# Thermistors.net
KiCad netlist of a schematic drawn in Altium Designer
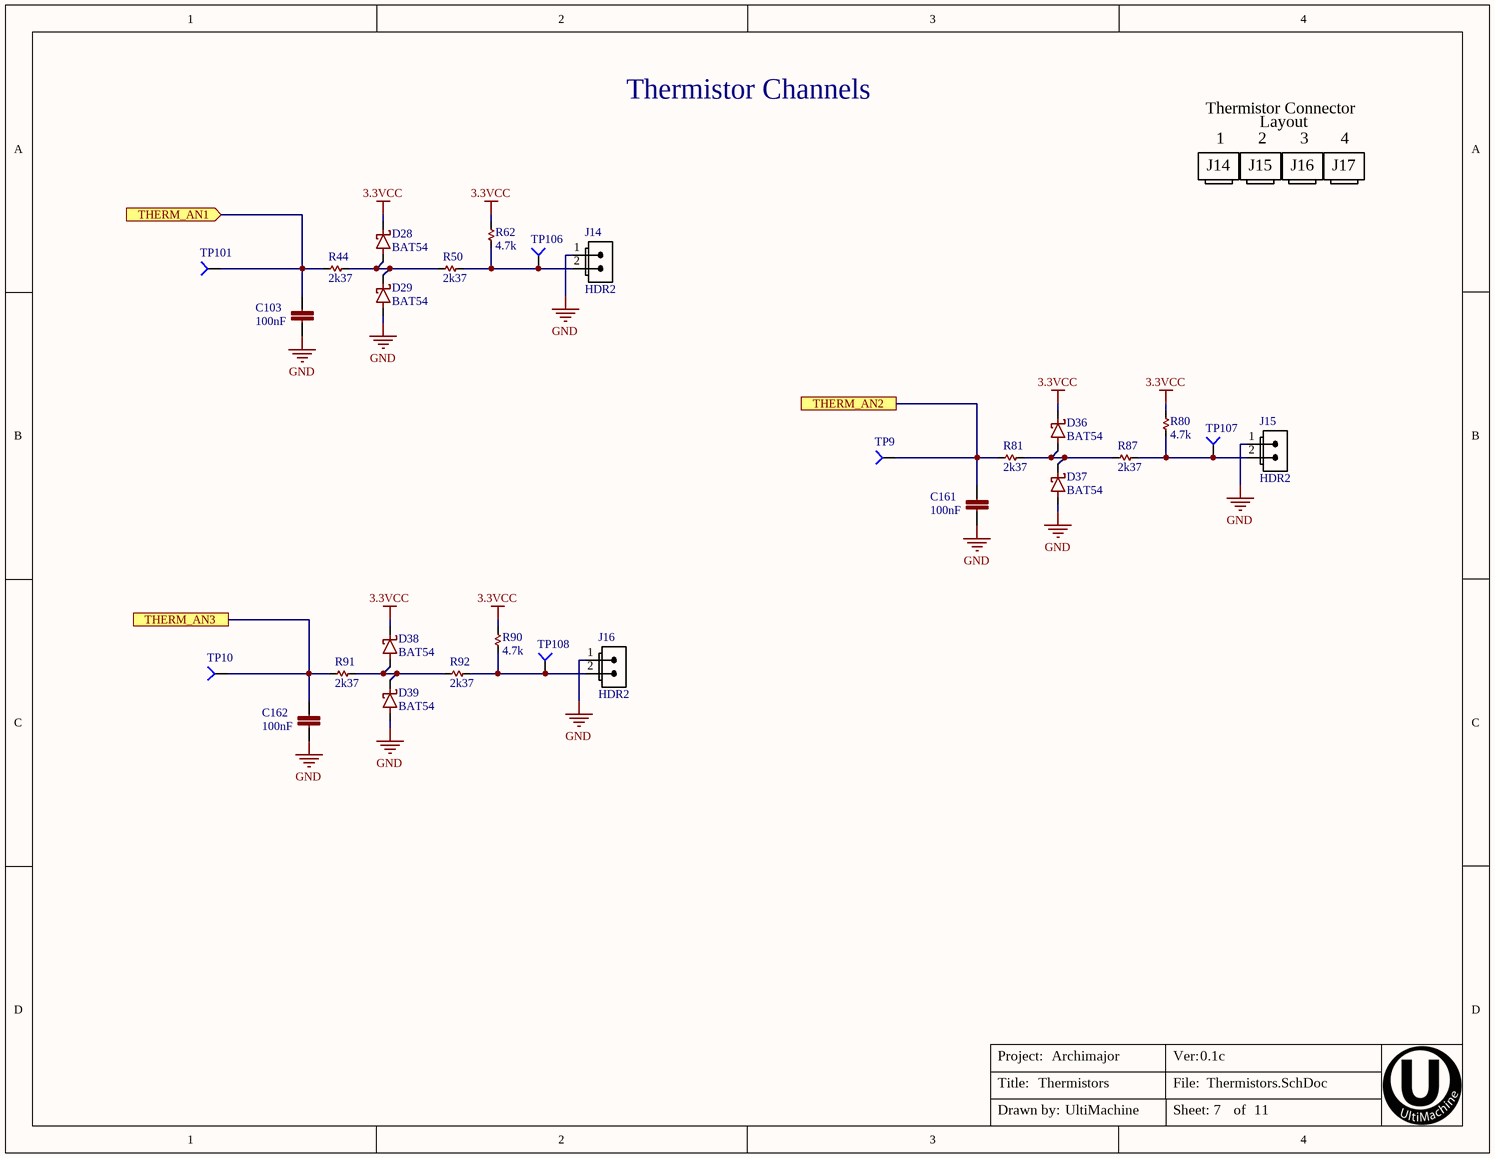
[diagram p0: Thermistors.SchDoc]

(export (version "E")
  (design (tool "Eeschema 10.0.6"))
  (components
    (comp (ref "C103")
      (value "100nF")
      (footprint "C0402")
      (description "CAP CER 0402 100nF 16V 10% X7R")
      (fields (field (name "MANUFACTURER") "Murata") (field (name "PART") "GRM155R71C104KA88D"))
      (libsource (lib "3Delight") (part "GRM155R71C104KA88D"))
    )
    (comp (ref "C161")
      (value "100nF")
      (footprint "C0402")
      (description "CAP CER 0402 100nF 16V 10% X7R")
      (fields (field (name "MANUFACTURER") "Murata") (field (name "PART") "GRM155R71C104KA88D"))
      (libsource (lib "3Delight") (part "GRM155R71C104KA88D"))
    )
    (comp (ref "C162")
      (value "100nF")
      (footprint "C0402")
      (description "CAP CER 0402 100nF 16V 10% X7R")
      (fields (field (name "MANUFACTURER") "Murata") (field (name "PART") "GRM155R71C104KA88D"))
      (libsource (lib "3Delight") (part "GRM155R71C104KA88D"))
    )
    (comp (ref "D28")
      (value "BAT54")
      (footprint "SOD523_IPC")
      (description "DIODE SCHOTTKY 30V 200MA SOD523")
      (fields (field (name "MANUFACTURER") "Diodes Incorporated") (field (name "PART") "BAT54WX-TP"))
      (libsource (lib "Diodes") (part "BAT54WX"))
    )
    (comp (ref "D29")
      (value "BAT54")
      (footprint "SOD523_IPC")
      (description "DIODE SCHOTTKY 30V 200MA SOD523")
      (fields (field (name "MANUFACTURER") "Diodes Incorporated") (field (name "PART") "BAT54WX-TP"))
      (libsource (lib "Diodes") (part "BAT54WX"))
    )
    (comp (ref "D36")
      (value "BAT54")
      (footprint "SOD523_IPC")
      (description "DIODE SCHOTTKY 30V 200MA SOD523")
      (fields (field (name "MANUFACTURER") "Diodes Incorporated") (field (name "PART") "BAT54WX-TP"))
      (libsource (lib "Diodes") (part "BAT54WX"))
    )
    (comp (ref "D37")
      (value "BAT54")
      (footprint "SOD523_IPC")
      (description "DIODE SCHOTTKY 30V 200MA SOD523")
      (fields (field (name "MANUFACTURER") "Diodes Incorporated") (field (name "PART") "BAT54WX-TP"))
      (libsource (lib "Diodes") (part "BAT54WX"))
    )
    (comp (ref "D38")
      (value "BAT54")
      (footprint "SOD523_IPC")
      (description "DIODE SCHOTTKY 30V 200MA SOD523")
      (fields (field (name "MANUFACTURER") "Diodes Incorporated") (field (name "PART") "BAT54WX-TP"))
      (libsource (lib "Diodes") (part "BAT54WX"))
    )
    (comp (ref "D39")
      (value "BAT54")
      (footprint "SOD523_IPC")
      (description "DIODE SCHOTTKY 30V 200MA SOD523")
      (fields (field (name "MANUFACTURER") "Diodes Incorporated") (field (name "PART") "BAT54WX-TP"))
      (libsource (lib "Diodes") (part "BAT54WX"))
    )
    (comp (ref "J14")
      (value "HDR2")
      (footprint "70543-01 PIN-IN-PASTE")
      (description "Connector 2pos - Pin in Paste")
      (fields (field (name "MANUFACTURER") "Molex") (field (name "PART") "0705430001"))
      (libsource (lib "Connectors") (part "CONN 2PIN VERT 0.1{dblquote} SHRD LOCKING PIP"))
    )
    (comp (ref "J15")
      (value "HDR2")
      (footprint "70543-01 PIN-IN-PASTE")
      (description "Connector 2pos - Pin in Paste")
      (fields (field (name "MANUFACTURER") "Molex") (field (name "PART") "0705430001"))
      (libsource (lib "Connectors") (part "CONN 2PIN VERT 0.1{dblquote} SHRD LOCKING PIP"))
    )
    (comp (ref "J16")
      (value "HDR2")
      (footprint "70543-01 PIN-IN-PASTE")
      (description "Connector 2pos - Pin in Paste")
      (fields (field (name "MANUFACTURER") "Molex") (field (name "PART") "0705430001"))
      (libsource (lib "Connectors") (part "CONN 2PIN VERT 0.1{dblquote} SHRD LOCKING PIP"))
    )
    (comp (ref "R44")
      (value "2k37")
      (footprint "R0402")
      (description "RES SMD 2.37K OHM 1% 1/16W 0402")
      (fields (field (name "MANUFACTURER") "Yageo") (field (name "PART") "RC0402FR-072K37L"))
      (libsource (lib "3Delight") (part "RC0402FR-072K37L"))
    )
    (comp (ref "R50")
      (value "2k37")
      (footprint "R0402")
      (description "RES SMD 2.37K OHM 1% 1/16W 0402")
      (fields (field (name "MANUFACTURER") "Yageo") (field (name "PART") "RC0402FR-072K37L"))
      (libsource (lib "3Delight") (part "RC0402FR-072K37L"))
    )
    (comp (ref "R62")
      (value "4.7k")
      (footprint "R0402")
      (description "RES SMD 4.7K OHM 1% 1/16W 0402")
      (fields (field (name "MANUFACTURER") "YAGEO") (field (name "PART") "RC0402FR-074K7L"))
      (libsource (lib "3Delight") (part "RC0402FR-074K7L"))
    )
    (comp (ref "R80")
      (value "4.7k")
      (footprint "R0402")
      (description "RES SMD 4.7K OHM 1% 1/16W 0402")
      (fields (field (name "MANUFACTURER") "YAGEO") (field (name "PART") "RC0402FR-074K7L"))
      (libsource (lib "3Delight") (part "RC0402FR-074K7L"))
    )
    (comp (ref "R81")
      (value "2k37")
      (footprint "R0402")
      (description "RES SMD 2.37K OHM 1% 1/16W 0402")
      (fields (field (name "MANUFACTURER") "Yageo") (field (name "PART") "RC0402FR-072K37L"))
      (libsource (lib "3Delight") (part "RC0402FR-072K37L"))
    )
    (comp (ref "R87")
      (value "2k37")
      (footprint "R0402")
      (description "RES SMD 2.37K OHM 1% 1/16W 0402")
      (fields (field (name "MANUFACTURER") "Yageo") (field (name "PART") "RC0402FR-072K37L"))
      (libsource (lib "3Delight") (part "RC0402FR-072K37L"))
    )
    (comp (ref "R90")
      (value "4.7k")
      (footprint "R0402")
      (description "RES SMD 4.7K OHM 1% 1/16W 0402")
      (fields (field (name "MANUFACTURER") "YAGEO") (field (name "PART") "RC0402FR-074K7L"))
      (libsource (lib "3Delight") (part "RC0402FR-074K7L"))
    )
    (comp (ref "R91")
      (value "2k37")
      (footprint "R0402")
      (description "RES SMD 2.37K OHM 1% 1/16W 0402")
      (fields (field (name "MANUFACTURER") "Yageo") (field (name "PART") "RC0402FR-072K37L"))
      (libsource (lib "3Delight") (part "RC0402FR-072K37L"))
    )
    (comp (ref "R92")
      (value "2k37")
      (footprint "R0402")
      (description "RES SMD 2.37K OHM 1% 1/16W 0402")
      (fields (field (name "MANUFACTURER") "Yageo") (field (name "PART") "RC0402FR-072K37L"))
      (libsource (lib "3Delight") (part "RC0402FR-072K37L"))
    )
    (comp (ref "TP9")
      (value "TP4")
      (footprint "TP-2")
      (description "Socket")
      (fields (field (name "PART") "NOTAPART-Testpoint"))
      (libsource (lib "Archim") (part "Socket"))
    )
    (comp (ref "TP10")
      (value "TP4")
      (footprint "TP-2")
      (description "Socket")
      (fields (field (name "PART") "NOTAPART-Testpoint"))
      (libsource (lib "Archim") (part "Socket"))
    )
    (comp (ref "TP101")
      (value "TP4")
      (footprint "TP-2")
      (description "Socket")
      (fields (field (name "PART") "NOTAPART-Testpoint"))
      (libsource (lib "Archim") (part "Socket"))
    )
    (comp (ref "TP106")
      (value "TP4")
      (footprint "TP-2")
      (description "Socket")
      (fields (field (name "PART") "NOTAPART-Testpoint"))
      (libsource (lib "Archim") (part "Socket"))
    )
    (comp (ref "TP107")
      (value "TP4")
      (footprint "TP-2")
      (description "Socket")
      (fields (field (name "PART") "NOTAPART-Testpoint"))
      (libsource (lib "Archim") (part "Socket"))
    )
    (comp (ref "TP108")
      (value "TP4")
      (footprint "TP-2")
      (description "Socket")
      (fields (field (name "PART") "NOTAPART-Testpoint"))
      (libsource (lib "Archim") (part "Socket"))
    )
  )
  (nets
    (net (code "1") (name "/THERM_AN1") (class "Default")
      (node (ref "C103") (pin "1") (pinfunction "1_1") (pintype "passive"))
      (node (ref "R44") (pin "1") (pinfunction "1_1") (pintype "passive"))
      (node (ref "TP101") (pin "1") (pinfunction "1_1") (pintype "passive"))
    )
    (net (code "2") (name "/THERM_AN2") (class "Default")
      (node (ref "C161") (pin "1") (pinfunction "1_1") (pintype "passive"))
      (node (ref "R81") (pin "1") (pinfunction "1_1") (pintype "passive"))
      (node (ref "TP9") (pin "1") (pinfunction "1_1") (pintype "passive"))
    )
    (net (code "3") (name "/THERM_AN3") (class "Default")
      (node (ref "C162") (pin "1") (pinfunction "1_1") (pintype "passive"))
      (node (ref "R91") (pin "1") (pinfunction "1_1") (pintype "passive"))
      (node (ref "TP10") (pin "1") (pinfunction "1_1") (pintype "passive"))
    )
    (net (code "4") (name "3.3VCC") (class "Default")
      (node (ref "D28") (pin "K") (pinfunction "K_K") (pintype "passive"))
      (node (ref "D36") (pin "K") (pinfunction "K_K") (pintype "passive"))
      (node (ref "D38") (pin "K") (pinfunction "K_K") (pintype "passive"))
      (node (ref "R62") (pin "2") (pinfunction "2_2") (pintype "passive"))
      (node (ref "R80") (pin "2") (pinfunction "2_2") (pintype "passive"))
      (node (ref "R90") (pin "2") (pinfunction "2_2") (pintype "passive"))
    )
    (net (code "5") (name "GND") (class "Default")
      (node (ref "C103") (pin "2") (pinfunction "2_2") (pintype "passive"))
      (node (ref "C161") (pin "2") (pinfunction "2_2") (pintype "passive"))
      (node (ref "C162") (pin "2") (pinfunction "2_2") (pintype "passive"))
      (node (ref "D29") (pin "A") (pinfunction "A_A") (pintype "passive"))
      (node (ref "D37") (pin "A") (pinfunction "A_A") (pintype "passive"))
      (node (ref "D39") (pin "A") (pinfunction "A_A") (pintype "passive"))
      (node (ref "J14") (pin "1") (pinfunction "S_1") (pintype "passive"))
      (node (ref "J15") (pin "1") (pinfunction "S_1") (pintype "passive"))
      (node (ref "J16") (pin "1") (pinfunction "S_1") (pintype "passive"))
    )
    (net (code "6") (name "Net-(D28-PadA)") (class "Default")
      (node (ref "D28") (pin "A") (pinfunction "A_A") (pintype "passive"))
      (node (ref "D29") (pin "K") (pinfunction "K_K") (pintype "passive"))
      (node (ref "R44") (pin "2") (pinfunction "2_2") (pintype "passive"))
      (node (ref "R50") (pin "1") (pinfunction "1_1") (pintype "passive"))
    )
    (net (code "7") (name "Net-(D36-PadA)") (class "Default")
      (node (ref "D36") (pin "A") (pinfunction "A_A") (pintype "passive"))
      (node (ref "D37") (pin "K") (pinfunction "K_K") (pintype "passive"))
      (node (ref "R81") (pin "2") (pinfunction "2_2") (pintype "passive"))
      (node (ref "R87") (pin "1") (pinfunction "1_1") (pintype "passive"))
    )
    (net (code "8") (name "Net-(D38-PadA)") (class "Default")
      (node (ref "D38") (pin "A") (pinfunction "A_A") (pintype "passive"))
      (node (ref "D39") (pin "K") (pinfunction "K_K") (pintype "passive"))
      (node (ref "R91") (pin "2") (pinfunction "2_2") (pintype "passive"))
      (node (ref "R92") (pin "1") (pinfunction "1_1") (pintype "passive"))
    )
    (net (code "9") (name "Net-(J14-S-Pad2)") (class "Default")
      (node (ref "J14") (pin "2") (pinfunction "S_2") (pintype "passive"))
      (node (ref "R50") (pin "2") (pinfunction "2_2") (pintype "passive"))
      (node (ref "R62") (pin "1") (pinfunction "1_1") (pintype "passive"))
      (node (ref "TP106") (pin "1") (pinfunction "1_1") (pintype "passive"))
    )
    (net (code "10") (name "Net-(J15-S-Pad2)") (class "Default")
      (node (ref "J15") (pin "2") (pinfunction "S_2") (pintype "passive"))
      (node (ref "R80") (pin "1") (pinfunction "1_1") (pintype "passive"))
      (node (ref "R87") (pin "2") (pinfunction "2_2") (pintype "passive"))
      (node (ref "TP107") (pin "1") (pinfunction "1_1") (pintype "passive"))
    )
    (net (code "11") (name "Net-(J16-S-Pad2)") (class "Default")
      (node (ref "J16") (pin "2") (pinfunction "S_2") (pintype "passive"))
      (node (ref "R90") (pin "1") (pinfunction "1_1") (pintype "passive"))
      (node (ref "R92") (pin "2") (pinfunction "2_2") (pintype "passive"))
      (node (ref "TP108") (pin "1") (pinfunction "1_1") (pintype "passive"))
    )
  )
)
